# esp_neopixel.net
KiCad netlist of a schematic drawn in EAGLE
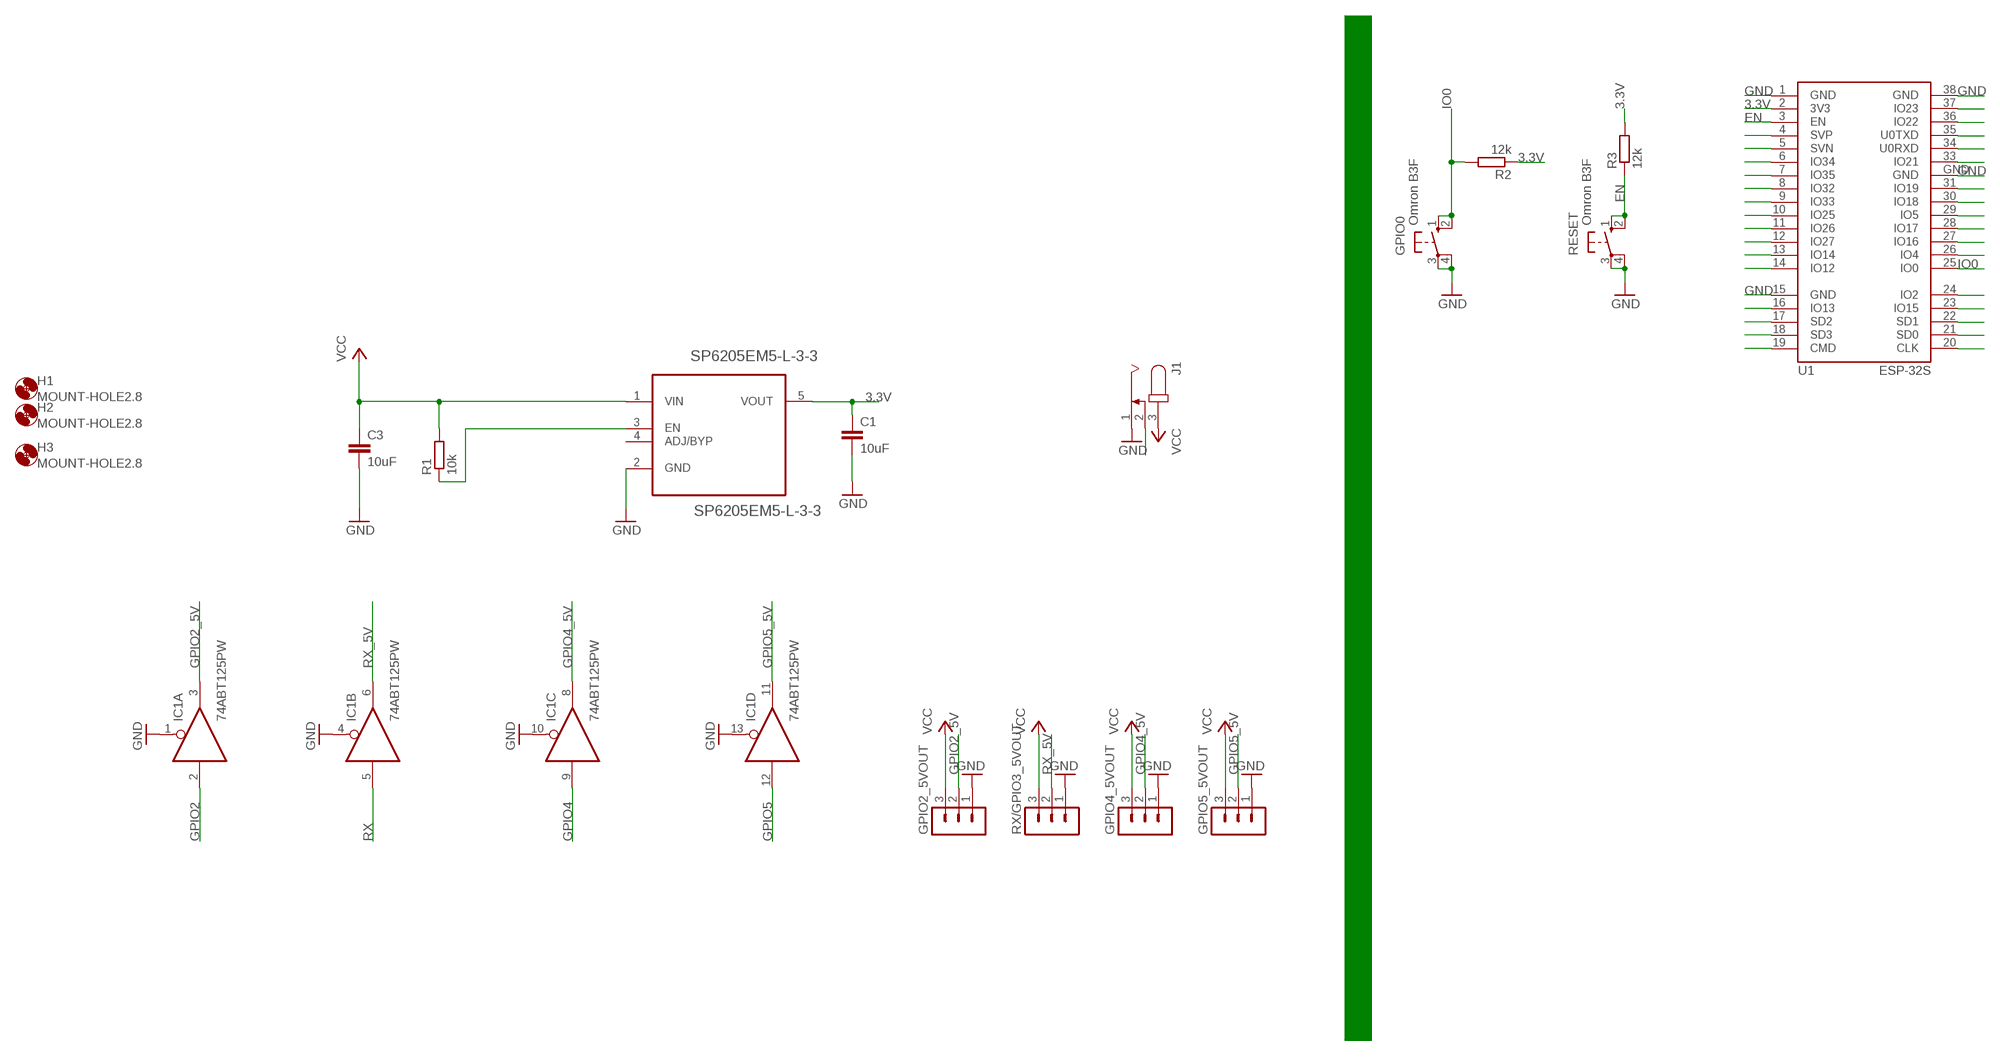
[diagram p0: schematic, sheet 1]

(export (version "E")
  (design (tool "Eeschema 10.0.6"))
  (components
    (comp (ref "C1")
      (value "10uF")
      (footprint "eagle-import:C0805K")
      (libsource (lib "eagle-import") (part "C-EUC0805K"))
    )
    (comp (ref "C3")
      (value "10uF")
      (footprint "eagle-import:C0805K")
      (libsource (lib "eagle-import") (part "C-EUC0805K"))
    )
    (comp (ref "GPIO0")
      (value "Omron B3F")
      (footprint "eagle-import:B3F-10XX")
      (fields (field (name "MPN") "B3F-1000"))
      (libsource (lib "eagle-import") (part "10-XX"))
    )
    (comp (ref "GPIO2_5VOUT")
      (value "MA03-1")
      (footprint "eagle-import:MA03-1")
      (libsource (lib "eagle-import") (part "MA03-1"))
    )
    (comp (ref "GPIO4_5VOUT")
      (value "MA03-1")
      (footprint "eagle-import:MA03-1")
      (libsource (lib "eagle-import") (part "MA03-1"))
    )
    (comp (ref "GPIO5_5VOUT")
      (value "MA03-1")
      (footprint "eagle-import:MA03-1")
      (libsource (lib "eagle-import") (part "MA03-1"))
    )
    (comp (ref "H1")
      (value "MOUNT-HOLE2.8")
      (footprint "eagle-import:2,8")
      (libsource (lib "eagle-import") (part "MOUNT-HOLE2.8"))
    )
    (comp (ref "H2")
      (value "MOUNT-HOLE2.8")
      (footprint "eagle-import:2,8")
      (libsource (lib "eagle-import") (part "MOUNT-HOLE2.8"))
    )
    (comp (ref "H3")
      (value "MOUNT-HOLE2.8")
      (footprint "eagle-import:2,8")
      (libsource (lib "eagle-import") (part "MOUNT-HOLE2.8"))
    )
    (comp (ref "IC1")
      (value "74ABT125PW")
      (footprint "eagle-import:TSSOP14")
      (libsource (lib "eagle-import") (part "74125PWABT"))
    )
    (comp (ref "J1")
      (value "JACK-PLUG1")
      (footprint "eagle-import:SPC4078")
      (libsource (lib "eagle-import") (part "JACK-PLUG1"))
    )
    (comp (ref "R1")
      (value "10k")
      (footprint "eagle-import:M0805")
      (libsource (lib "eagle-import") (part "R-EU_M0805"))
    )
    (comp (ref "R2")
      (value "12k")
      (footprint "eagle-import:M0805")
      (libsource (lib "eagle-import") (part "R-EU_M0805"))
    )
    (comp (ref "R3")
      (value "12k")
      (footprint "eagle-import:M0805")
      (libsource (lib "eagle-import") (part "R-EU_M0805"))
    )
    (comp (ref "RESET")
      (value "Omron B3F")
      (footprint "eagle-import:B3F-10XX")
      (fields (field (name "MPN") "B3F-1000"))
      (libsource (lib "eagle-import") (part "10-XX"))
    )
    (comp (ref "RX/GPIO3_5VOUT")
      (value "MA03-1")
      (footprint "eagle-import:MA03-1")
      (libsource (lib "eagle-import") (part "MA03-1"))
    )
    (comp (ref "SP6205EM5-L-3-3")
      (value "SP6205EM5-L-3-3")
      (footprint "eagle-import:SOT95P280X145-5N")
      (fields (field (name "MPN") "SPX3819M5-L"))
      (libsource (lib "eagle-import") (part "SPX3819M5-L"))
    )
    (comp (ref "U1")
      (value "ESP-32S")
      (footprint "eagle-import:ESP-32S")
      (libsource (lib "eagle-import") (part "ESP-32S"))
    )
  )
  (nets
    (net (code "1") (name "/3.3V") (class "Default")
      (node (ref "C1") (pin "1") (pinfunction "1_1") (pintype "passive"))
      (node (ref "R2") (pin "1") (pinfunction "1_1") (pintype "passive"))
      (node (ref "R3") (pin "2") (pinfunction "2_2") (pintype "passive"))
      (node (ref "SP6205EM5-L-3-3") (pin "5") (pinfunction "VOUT_5") (pintype "output"))
      (node (ref "U1") (pin "2") (pinfunction "3V3_2") (pintype "power_in"))
    )
    (net (code "2") (name "/EN") (class "Default")
      (node (ref "R3") (pin "1") (pinfunction "1_1") (pintype "passive"))
      (node (ref "RESET") (pin "1") (pinfunction "S_1") (pintype "passive"))
      (node (ref "RESET") (pin "2") (pinfunction "S1_2") (pintype "passive"))
      (node (ref "U1") (pin "3") (pinfunction "EN_3") (pintype "input"))
    )
    (net (code "3") (name "/GPIO2") (class "Default")
      (node (ref "IC1") (pin "2") (pinfunction "I_2") (pintype "input"))
    )
    (net (code "4") (name "/GPIO2_5V") (class "Default")
      (node (ref "GPIO2_5VOUT") (pin "2") (pinfunction "2_2") (pintype "passive"))
      (node (ref "IC1") (pin "3") (pinfunction "O_3") (pintype "tri_state"))
    )
    (net (code "5") (name "/GPIO4") (class "Default")
      (node (ref "IC1") (pin "9") (pinfunction "I_9") (pintype "input"))
    )
    (net (code "6") (name "/GPIO4_5V") (class "Default")
      (node (ref "GPIO4_5VOUT") (pin "2") (pinfunction "2_2") (pintype "passive"))
      (node (ref "IC1") (pin "8") (pinfunction "O_8") (pintype "tri_state"))
    )
    (net (code "7") (name "/GPIO5") (class "Default")
      (node (ref "IC1") (pin "12") (pinfunction "I_12") (pintype "input"))
    )
    (net (code "8") (name "/GPIO5_5V") (class "Default")
      (node (ref "GPIO5_5VOUT") (pin "2") (pinfunction "2_2") (pintype "passive"))
      (node (ref "IC1") (pin "11") (pinfunction "O_11") (pintype "tri_state"))
    )
    (net (code "9") (name "/IO0") (class "Default")
      (node (ref "GPIO0") (pin "1") (pinfunction "S_1") (pintype "passive"))
      (node (ref "GPIO0") (pin "2") (pinfunction "S1_2") (pintype "passive"))
      (node (ref "R2") (pin "2") (pinfunction "2_2") (pintype "passive"))
      (node (ref "U1") (pin "25") (pinfunction "IO0_25") (pintype "bidirectional"))
    )
    (net (code "10") (name "/RX") (class "Default")
      (node (ref "IC1") (pin "5") (pinfunction "I_5") (pintype "input"))
    )
    (net (code "11") (name "/RX_5V") (class "Default")
      (node (ref "IC1") (pin "6") (pinfunction "O_6") (pintype "tri_state"))
      (node (ref "RX/GPIO3_5VOUT") (pin "2") (pinfunction "2_2") (pintype "passive"))
    )
    (net (code "12") (name "GND") (class "Default")
      (node (ref "C1") (pin "2") (pinfunction "2_2") (pintype "passive"))
      (node (ref "C3") (pin "2") (pinfunction "2_2") (pintype "passive"))
      (node (ref "GPIO0") (pin "3") (pinfunction "P_3") (pintype "passive"))
      (node (ref "GPIO0") (pin "4") (pinfunction "P1_4") (pintype "passive"))
      (node (ref "GPIO2_5VOUT") (pin "1") (pinfunction "1_1") (pintype "passive"))
      (node (ref "GPIO4_5VOUT") (pin "1") (pinfunction "1_1") (pintype "passive"))
      (node (ref "GPIO5_5VOUT") (pin "1") (pinfunction "1_1") (pintype "passive"))
      (node (ref "IC1") (pin "1") (pinfunction "OE_1") (pintype "input"))
      (node (ref "IC1") (pin "10") (pinfunction "OE_10") (pintype "input"))
      (node (ref "IC1") (pin "13") (pinfunction "OE_13") (pintype "input"))
      (node (ref "IC1") (pin "4") (pinfunction "OE_4") (pintype "input"))
      (node (ref "J1") (pin "1") (pinfunction "1_1") (pintype "passive"))
      (node (ref "RESET") (pin "3") (pinfunction "P_3") (pintype "passive"))
      (node (ref "RESET") (pin "4") (pinfunction "P1_4") (pintype "passive"))
      (node (ref "RX/GPIO3_5VOUT") (pin "1") (pinfunction "1_1") (pintype "passive"))
      (node (ref "SP6205EM5-L-3-3") (pin "2") (pinfunction "GND_2") (pintype "passive"))
      (node (ref "U1") (pin "1") (pinfunction "GND_1") (pintype "power_in"))
      (node (ref "U1") (pin "15") (pinfunction "GND_15") (pintype "power_in"))
      (node (ref "U1") (pin "38") (pinfunction "GND_38") (pintype "power_in"))
      (node (ref "U1") (pin "GND") (pinfunction "GND_GND") (pintype "power_in"))
    )
    (net (code "13") (name "Net-(SP6205EM5-L-3-3-EN)") (class "Default")
      (node (ref "R1") (pin "1") (pinfunction "1_1") (pintype "passive"))
      (node (ref "SP6205EM5-L-3-3") (pin "3") (pinfunction "EN_3") (pintype "input"))
    )
    (net (code "14") (name "VCC") (class "Default")
      (node (ref "C3") (pin "1") (pinfunction "1_1") (pintype "passive"))
      (node (ref "GPIO2_5VOUT") (pin "3") (pinfunction "3_3") (pintype "passive"))
      (node (ref "GPIO4_5VOUT") (pin "3") (pinfunction "3_3") (pintype "passive"))
      (node (ref "GPIO5_5VOUT") (pin "3") (pinfunction "3_3") (pintype "passive"))
      (node (ref "J1") (pin "3") (pinfunction "3_3") (pintype "passive"))
      (node (ref "R1") (pin "2") (pinfunction "2_2") (pintype "passive"))
      (node (ref "RX/GPIO3_5VOUT") (pin "3") (pinfunction "3_3") (pintype "passive"))
      (node (ref "SP6205EM5-L-3-3") (pin "1") (pinfunction "VIN_1") (pintype "power_in"))
    )
    (net (code "15") (name "unconnected-(J1-Pad2)") (class "Default")
      (node (ref "J1") (pin "2") (pinfunction "2_2") (pintype "passive"))
    )
    (net (code "16") (name "unconnected-(SP6205EM5-L-3-3-ADJ{slash}BYP-Pad4)") (class "Default")
      (node (ref "SP6205EM5-L-3-3") (pin "4") (pinfunction "ADJ/BYP_4") (pintype "passive"))
    )
    (net (code "17") (name "unconnected-(U1-CLK-Pad20)") (class "Default")
      (node (ref "U1") (pin "20") (pinfunction "CLK_20") (pintype "bidirectional"))
    )
    (net (code "18") (name "unconnected-(U1-CMD-Pad19)") (class "Default")
      (node (ref "U1") (pin "19") (pinfunction "CMD_19") (pintype "bidirectional"))
    )
    (net (code "19") (name "unconnected-(U1-IO2-Pad24)") (class "Default")
      (node (ref "U1") (pin "24") (pinfunction "IO2_24") (pintype "bidirectional"))
    )
    (net (code "20") (name "unconnected-(U1-IO4-Pad26)") (class "Default")
      (node (ref "U1") (pin "26") (pinfunction "IO4_26") (pintype "bidirectional"))
    )
    (net (code "21") (name "unconnected-(U1-IO5-Pad29)") (class "Default")
      (node (ref "U1") (pin "29") (pinfunction "IO5_29") (pintype "bidirectional"))
    )
    (net (code "22") (name "unconnected-(U1-IO12-Pad14)") (class "Default")
      (node (ref "U1") (pin "14") (pinfunction "IO12_14") (pintype "bidirectional"))
    )
    (net (code "23") (name "unconnected-(U1-IO13-Pad16)") (class "Default")
      (node (ref "U1") (pin "16") (pinfunction "IO13_16") (pintype "bidirectional"))
    )
    (net (code "24") (name "unconnected-(U1-IO14-Pad13)") (class "Default")
      (node (ref "U1") (pin "13") (pinfunction "IO14_13") (pintype "bidirectional"))
    )
    (net (code "25") (name "unconnected-(U1-IO15-Pad23)") (class "Default")
      (node (ref "U1") (pin "23") (pinfunction "IO15_23") (pintype "bidirectional"))
    )
    (net (code "26") (name "unconnected-(U1-IO16-Pad27)") (class "Default")
      (node (ref "U1") (pin "27") (pinfunction "IO16_27") (pintype "bidirectional"))
    )
    (net (code "27") (name "unconnected-(U1-IO17-Pad28)") (class "Default")
      (node (ref "U1") (pin "28") (pinfunction "IO17_28") (pintype "bidirectional"))
    )
    (net (code "28") (name "unconnected-(U1-IO18-Pad30)") (class "Default")
      (node (ref "U1") (pin "30") (pinfunction "IO18_30") (pintype "bidirectional"))
    )
    (net (code "29") (name "unconnected-(U1-IO19-Pad31)") (class "Default")
      (node (ref "U1") (pin "31") (pinfunction "IO19_31") (pintype "bidirectional"))
    )
    (net (code "30") (name "unconnected-(U1-IO21-Pad33)") (class "Default")
      (node (ref "U1") (pin "33") (pinfunction "IO21_33") (pintype "bidirectional"))
    )
    (net (code "31") (name "unconnected-(U1-IO22-Pad36)") (class "Default")
      (node (ref "U1") (pin "36") (pinfunction "IO22_36") (pintype "bidirectional"))
    )
    (net (code "32") (name "unconnected-(U1-IO23-Pad37)") (class "Default")
      (node (ref "U1") (pin "37") (pinfunction "IO23_37") (pintype "bidirectional"))
    )
    (net (code "33") (name "unconnected-(U1-IO25-Pad10)") (class "Default")
      (node (ref "U1") (pin "10") (pinfunction "IO25_10") (pintype "bidirectional"))
    )
    (net (code "34") (name "unconnected-(U1-IO26-Pad11)") (class "Default")
      (node (ref "U1") (pin "11") (pinfunction "IO26_11") (pintype "bidirectional"))
    )
    (net (code "35") (name "unconnected-(U1-IO27-Pad12)") (class "Default")
      (node (ref "U1") (pin "12") (pinfunction "IO27_12") (pintype "bidirectional"))
    )
    (net (code "36") (name "unconnected-(U1-IO32-Pad8)") (class "Default")
      (node (ref "U1") (pin "8") (pinfunction "IO32_8") (pintype "bidirectional"))
    )
    (net (code "37") (name "unconnected-(U1-IO33-Pad9)") (class "Default")
      (node (ref "U1") (pin "9") (pinfunction "IO33_9") (pintype "bidirectional"))
    )
    (net (code "38") (name "unconnected-(U1-IO34-Pad6)") (class "Default")
      (node (ref "U1") (pin "6") (pinfunction "IO34_6") (pintype "bidirectional"))
    )
    (net (code "39") (name "unconnected-(U1-IO35-Pad7)") (class "Default")
      (node (ref "U1") (pin "7") (pinfunction "IO35_7") (pintype "bidirectional"))
    )
    (net (code "40") (name "unconnected-(U1-SD0-Pad21)") (class "Default")
      (node (ref "U1") (pin "21") (pinfunction "SD0_21") (pintype "bidirectional"))
    )
    (net (code "41") (name "unconnected-(U1-SD1-Pad22)") (class "Default")
      (node (ref "U1") (pin "22") (pinfunction "SD1_22") (pintype "bidirectional"))
    )
    (net (code "42") (name "unconnected-(U1-SD2-Pad17)") (class "Default")
      (node (ref "U1") (pin "17") (pinfunction "SD2_17") (pintype "bidirectional"))
    )
    (net (code "43") (name "unconnected-(U1-SD3-Pad18)") (class "Default")
      (node (ref "U1") (pin "18") (pinfunction "SD3_18") (pintype "bidirectional"))
    )
    (net (code "44") (name "unconnected-(U1-SVN-Pad5)") (class "Default")
      (node (ref "U1") (pin "5") (pinfunction "SVN_5") (pintype "bidirectional"))
    )
    (net (code "45") (name "unconnected-(U1-SVP-Pad4)") (class "Default")
      (node (ref "U1") (pin "4") (pinfunction "SVP_4") (pintype "bidirectional"))
    )
    (net (code "46") (name "unconnected-(U1-U0RXD-Pad34)") (class "Default")
      (node (ref "U1") (pin "34") (pinfunction "U0RXD_34") (pintype "bidirectional"))
    )
    (net (code "47") (name "unconnected-(U1-U0TXD-Pad35)") (class "Default")
      (node (ref "U1") (pin "35") (pinfunction "U0TXD_35") (pintype "bidirectional"))
    )
  )
)
